# 16A-01.net
KiCad netlist of a schematic drawn in EAGLE
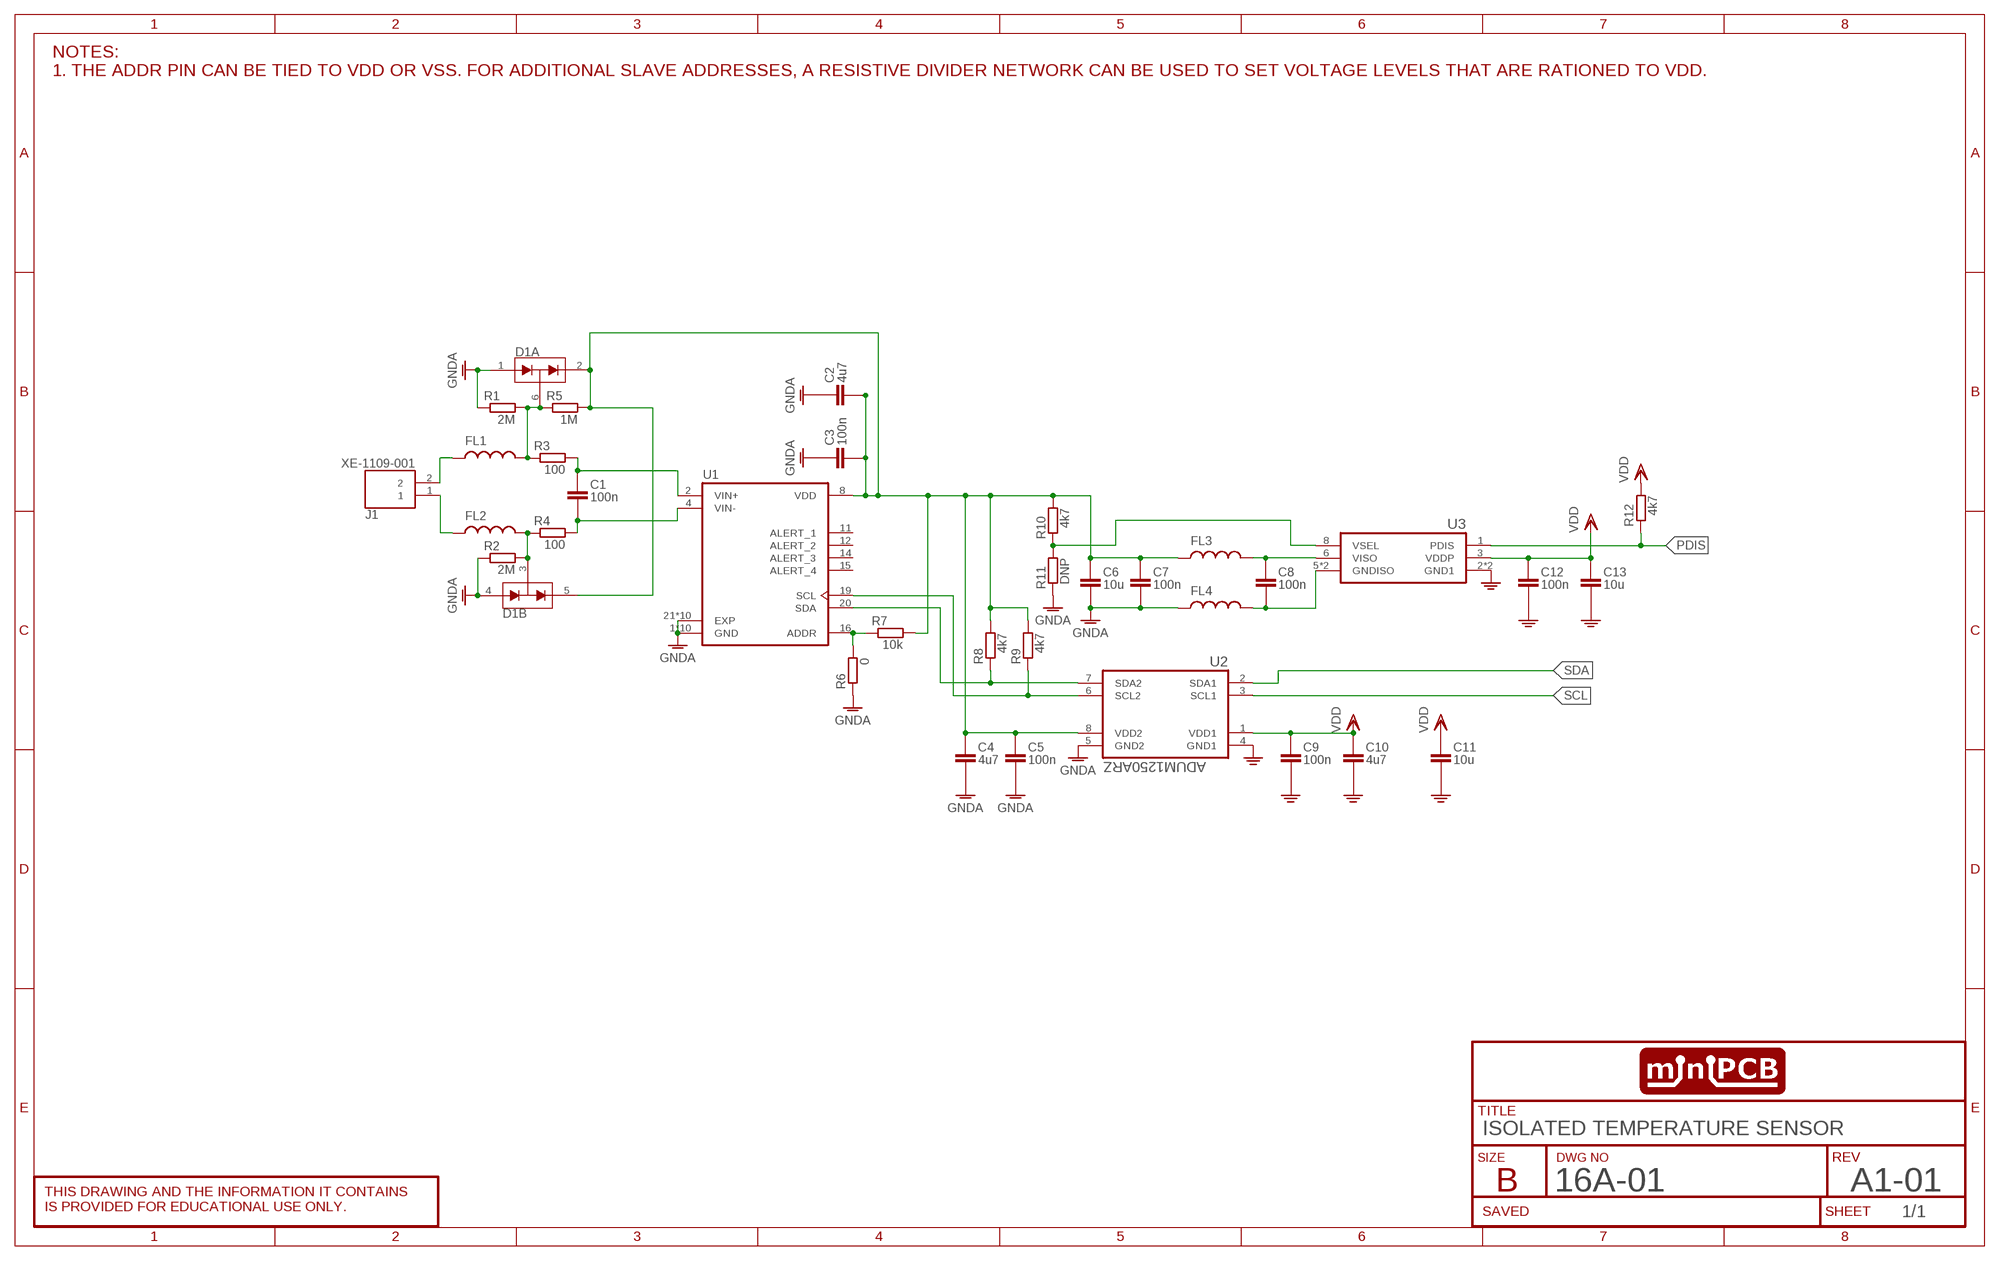
[diagram p0: schematic, sheet 1]

(export (version "E")
  (design (tool "Eeschema 10.0.6"))
  (components
    (comp (ref "C1")
      (value "100n")
      (footprint "eagle-import:C0402")
      (libsource (lib "eagle-import") (part "CAPACITOR0402"))
    )
    (comp (ref "C2")
      (value "4u7")
      (footprint "eagle-import:C0402")
      (libsource (lib "eagle-import") (part "CAPACITOR0402"))
    )
    (comp (ref "C3")
      (value "100n")
      (footprint "eagle-import:C0402")
      (libsource (lib "eagle-import") (part "CAPACITOR0402"))
    )
    (comp (ref "C4")
      (value "4u7")
      (footprint "eagle-import:C0402")
      (libsource (lib "eagle-import") (part "CAPACITOR0402"))
    )
    (comp (ref "C5")
      (value "100n")
      (footprint "eagle-import:C0402")
      (libsource (lib "eagle-import") (part "CAPACITOR0402"))
    )
    (comp (ref "C6")
      (value "10u")
      (footprint "eagle-import:C0805")
      (libsource (lib "eagle-import") (part "CAPACITORSMD"))
    )
    (comp (ref "C7")
      (value "100n")
      (footprint "eagle-import:C0402")
      (libsource (lib "eagle-import") (part "CAPACITOR0402"))
    )
    (comp (ref "C8")
      (value "100n")
      (footprint "eagle-import:C0402")
      (libsource (lib "eagle-import") (part "CAPACITOR0402"))
    )
    (comp (ref "C9")
      (value "100n")
      (footprint "eagle-import:C0402")
      (libsource (lib "eagle-import") (part "CAPACITOR0402"))
    )
    (comp (ref "C10")
      (value "4u7")
      (footprint "eagle-import:C0402")
      (libsource (lib "eagle-import") (part "CAPACITOR0402"))
    )
    (comp (ref "C11")
      (value "10u")
      (footprint "eagle-import:C0805")
      (libsource (lib "eagle-import") (part "CAPACITORSMD"))
    )
    (comp (ref "C12")
      (value "100n")
      (footprint "eagle-import:C0402")
      (libsource (lib "eagle-import") (part "CAPACITOR0402"))
    )
    (comp (ref "C13")
      (value "10u")
      (footprint "eagle-import:C0805")
      (libsource (lib "eagle-import") (part "CAPACITORSMD"))
    )
    (comp (ref "D1")
      (value "SDA004-7")
      (footprint "eagle-import:SOT363")
      (libsource (lib "eagle-import") (part "SDA004-7"))
    )
    (comp (ref "FL1")
      (value "BLM03HG601SZ1D")
      (footprint "eagle-import:R0402")
      (libsource (lib "eagle-import") (part "BLM03HG601SZ1D"))
    )
    (comp (ref "FL2")
      (value "BLM03HG601SZ1D")
      (footprint "eagle-import:R0402")
      (libsource (lib "eagle-import") (part "BLM03HG601SZ1D"))
    )
    (comp (ref "FL3")
      (value "BLM03HG601SZ1D")
      (footprint "eagle-import:R0402")
      (libsource (lib "eagle-import") (part "BLM03HG601SZ1D"))
    )
    (comp (ref "FL4")
      (value "BLM03HG601SZ1D")
      (footprint "eagle-import:R0402")
      (libsource (lib "eagle-import") (part "BLM03HG601SZ1D"))
    )
    (comp (ref "J1")
      (value "XE-1109-001")
      (footprint "eagle-import:XE-1109-001")
      (libsource (lib "eagle-import") (part "XE-1109-001"))
    )
    (comp (ref "R1")
      (value "2M")
      (footprint "eagle-import:R0402")
      (libsource (lib "eagle-import") (part "RESISTOR0402"))
    )
    (comp (ref "R2")
      (value "2M")
      (footprint "eagle-import:R0402")
      (libsource (lib "eagle-import") (part "RESISTOR0402"))
    )
    (comp (ref "R3")
      (value "100")
      (footprint "eagle-import:R0402")
      (libsource (lib "eagle-import") (part "RESISTOR0402"))
    )
    (comp (ref "R4")
      (value "100")
      (footprint "eagle-import:R0402")
      (libsource (lib "eagle-import") (part "RESISTOR0402"))
    )
    (comp (ref "R5")
      (value "1M")
      (footprint "eagle-import:R0402")
      (libsource (lib "eagle-import") (part "RESISTOR0402"))
    )
    (comp (ref "R6")
      (value "0")
      (footprint "eagle-import:R0402")
      (libsource (lib "eagle-import") (part "RESISTOR0402"))
    )
    (comp (ref "R7")
      (value "10k")
      (footprint "eagle-import:R0402")
      (libsource (lib "eagle-import") (part "RESISTOR0402"))
    )
    (comp (ref "R8")
      (value "4k7")
      (footprint "eagle-import:R0402")
      (libsource (lib "eagle-import") (part "RESISTOR0402"))
    )
    (comp (ref "R9")
      (value "4k7")
      (footprint "eagle-import:R0402")
      (libsource (lib "eagle-import") (part "RESISTOR0402"))
    )
    (comp (ref "R10")
      (value "4k7")
      (footprint "eagle-import:R0402")
      (libsource (lib "eagle-import") (part "RESISTOR0402"))
    )
    (comp (ref "R11")
      (value "DNP")
      (footprint "eagle-import:R0402")
      (libsource (lib "eagle-import") (part "RESISTOR0402"))
    )
    (comp (ref "R12")
      (value "4k7")
      (footprint "eagle-import:R0402")
      (libsource (lib "eagle-import") (part "RESISTOR0402"))
    )
    (comp (ref "U1")
      (value "MCP9600T-I/MX")
      (footprint "eagle-import:QFN65P500X500X100-21N_MCP9600T-I_MX")
      (fields (field (name "MF") "Microchip Technology"))
      (libsource (lib "eagle-import") (part "MCP9600T-I/MX"))
    )
    (comp (ref "U2")
      (value "ADUM1250ARZ")
      (footprint "eagle-import:SOIC127P600X175-8N")
      (fields (field (name "MF") "Analog Devices"))
      (libsource (lib "eagle-import") (part "ADUM1250ARZ"))
    )
    (comp (ref "U3")
      (value "ADUM6280")
      (footprint "eagle-import:SOIC127P600X175-8N")
      (libsource (lib "eagle-import") (part "ADUM6280"))
    )
  )
  (nets
    (net (code "1") (name "GND") (class "Default")
      (node (ref "C10") (pin "2") (pinfunction "-_2") (pintype "passive"))
      (node (ref "C11") (pin "2ASDF") (pinfunction "-_2ASDF") (pintype "passive"))
      (node (ref "C12") (pin "2") (pinfunction "-_2") (pintype "passive"))
      (node (ref "C13") (pin "2ASDF") (pinfunction "-_2ASDF") (pintype "passive"))
      (node (ref "C9") (pin "2") (pinfunction "-_2") (pintype "passive"))
      (node (ref "U2") (pin "4") (pinfunction "GND1_4") (pintype "passive"))
      (node (ref "U3") (pin "2") (pinfunction "GND1_2") (pintype "passive"))
      (node (ref "U3") (pin "4") (pinfunction "GND1_4") (pintype "passive"))
    )
    (net (code "2") (name "GNDA") (class "Default")
      (node (ref "C2") (pin "1") (pinfunction "+_1") (pintype "passive"))
      (node (ref "C3") (pin "1") (pinfunction "+_1") (pintype "passive"))
      (node (ref "C4") (pin "2") (pinfunction "-_2") (pintype "passive"))
      (node (ref "C5") (pin "2") (pinfunction "-_2") (pintype "passive"))
      (node (ref "C6") (pin "2ASDF") (pinfunction "-_2ASDF") (pintype "passive"))
      (node (ref "C7") (pin "2") (pinfunction "-_2") (pintype "passive"))
      (node (ref "D1") (pin "1") (pinfunction "A1_1") (pintype "bidirectional"))
      (node (ref "D1") (pin "4") (pinfunction "A1_4") (pintype "bidirectional"))
      (node (ref "FL4") (pin "1") (pinfunction "1_1") (pintype "passive"))
      (node (ref "R1") (pin "1") (pinfunction "1_1") (pintype "passive"))
      (node (ref "R11") (pin "1") (pinfunction "1_1") (pintype "passive"))
      (node (ref "R2") (pin "1") (pinfunction "1_1") (pintype "passive"))
      (node (ref "R6") (pin "1") (pinfunction "1_1") (pintype "passive"))
      (node (ref "U1") (pin "1") (pinfunction "GND_1") (pintype "power_in"))
      (node (ref "U1") (pin "10") (pinfunction "GND_10") (pintype "power_in"))
      (node (ref "U1") (pin "13") (pinfunction "GND_13") (pintype "power_in"))
      (node (ref "U1") (pin "17") (pinfunction "GND_17") (pintype "power_in"))
      (node (ref "U1") (pin "18") (pinfunction "GND_18") (pintype "power_in"))
      (node (ref "U1") (pin "21") (pinfunction "EXP_21") (pintype "power_in"))
      (node (ref "U1") (pin "22") (pinfunction "EXP_22") (pintype "power_in"))
      (node (ref "U1") (pin "23") (pinfunction "EXP_23") (pintype "power_in"))
      (node (ref "U1") (pin "24") (pinfunction "EXP_24") (pintype "power_in"))
      (node (ref "U1") (pin "25") (pinfunction "EXP_25") (pintype "power_in"))
      (node (ref "U1") (pin "26") (pinfunction "EXP_26") (pintype "power_in"))
      (node (ref "U1") (pin "27") (pinfunction "EXP_27") (pintype "power_in"))
      (node (ref "U1") (pin "28") (pinfunction "EXP_28") (pintype "power_in"))
      (node (ref "U1") (pin "29") (pinfunction "EXP_29") (pintype "power_in"))
      (node (ref "U1") (pin "3") (pinfunction "GND_3") (pintype "power_in"))
      (node (ref "U1") (pin "30") (pinfunction "EXP_30") (pintype "power_in"))
      (node (ref "U1") (pin "5") (pinfunction "GND_5") (pintype "power_in"))
      (node (ref "U1") (pin "6") (pinfunction "GND_6") (pintype "power_in"))
      (node (ref "U1") (pin "7") (pinfunction "GND_7") (pintype "power_in"))
      (node (ref "U1") (pin "9") (pinfunction "GND_9") (pintype "power_in"))
      (node (ref "U2") (pin "5") (pinfunction "GND2_5") (pintype "passive"))
    )
    (net (code "3") (name "Net-(C1-+)") (class "Default")
      (node (ref "C1") (pin "1") (pinfunction "+_1") (pintype "passive"))
      (node (ref "R3") (pin "2") (pinfunction "2_2") (pintype "passive"))
      (node (ref "U1") (pin "2") (pinfunction "VIN+_2") (pintype "input"))
    )
    (net (code "4") (name "Net-(C1--)") (class "Default")
      (node (ref "C1") (pin "2") (pinfunction "-_2") (pintype "passive"))
      (node (ref "R4") (pin "2") (pinfunction "2_2") (pintype "passive"))
      (node (ref "U1") (pin "4") (pinfunction "VIN-_4") (pintype "input"))
    )
    (net (code "5") (name "Net-(C2--)") (class "Default")
      (node (ref "C2") (pin "2") (pinfunction "-_2") (pintype "passive"))
      (node (ref "C3") (pin "2") (pinfunction "-_2") (pintype "passive"))
      (node (ref "C4") (pin "1") (pinfunction "+_1") (pintype "passive"))
      (node (ref "C5") (pin "1") (pinfunction "+_1") (pintype "passive"))
      (node (ref "C6") (pin "1ASD") (pinfunction "+_1ASD") (pintype "passive"))
      (node (ref "C7") (pin "1") (pinfunction "+_1") (pintype "passive"))
      (node (ref "D1") (pin "2") (pinfunction "C2_2") (pintype "bidirectional"))
      (node (ref "D1") (pin "5") (pinfunction "C2_5") (pintype "bidirectional"))
      (node (ref "FL3") (pin "1") (pinfunction "1_1") (pintype "passive"))
      (node (ref "R10") (pin "2") (pinfunction "2_2") (pintype "passive"))
      (node (ref "R5") (pin "2") (pinfunction "2_2") (pintype "passive"))
      (node (ref "R7") (pin "2") (pinfunction "2_2") (pintype "passive"))
      (node (ref "R8") (pin "2") (pinfunction "2_2") (pintype "passive"))
      (node (ref "R9") (pin "2") (pinfunction "2_2") (pintype "passive"))
      (node (ref "U1") (pin "8") (pinfunction "VDD_8") (pintype "power_in"))
      (node (ref "U2") (pin "8") (pinfunction "VDD2_8") (pintype "power_in"))
    )
    (net (code "6") (name "Net-(C8-+)") (class "Default")
      (node (ref "C8") (pin "1") (pinfunction "+_1") (pintype "passive"))
      (node (ref "FL3") (pin "2") (pinfunction "2_2") (pintype "passive"))
      (node (ref "U3") (pin "6") (pinfunction "VISO_6") (pintype "power_in"))
    )
    (net (code "7") (name "Net-(C8--)") (class "Default")
      (node (ref "C8") (pin "2") (pinfunction "-_2") (pintype "passive"))
      (node (ref "FL4") (pin "2") (pinfunction "2_2") (pintype "passive"))
      (node (ref "U3") (pin "5") (pinfunction "GNDISO_5") (pintype "passive"))
      (node (ref "U3") (pin "7") (pinfunction "GNDISO_7") (pintype "passive"))
    )
    (net (code "8") (name "Net-(D1A-COM)") (class "Default")
      (node (ref "D1") (pin "6") (pinfunction "COM_6") (pintype "bidirectional"))
      (node (ref "FL1") (pin "2") (pinfunction "2_2") (pintype "passive"))
      (node (ref "R1") (pin "2") (pinfunction "2_2") (pintype "passive"))
      (node (ref "R3") (pin "1") (pinfunction "1_1") (pintype "passive"))
      (node (ref "R5") (pin "1") (pinfunction "1_1") (pintype "passive"))
    )
    (net (code "9") (name "Net-(D1B-COM)") (class "Default")
      (node (ref "D1") (pin "3") (pinfunction "COM_3") (pintype "bidirectional"))
      (node (ref "FL2") (pin "2") (pinfunction "2_2") (pintype "passive"))
      (node (ref "R2") (pin "2") (pinfunction "2_2") (pintype "passive"))
      (node (ref "R4") (pin "1") (pinfunction "1_1") (pintype "passive"))
    )
    (net (code "10") (name "Net-(FL1-Pad1)") (class "Default")
      (node (ref "FL1") (pin "1") (pinfunction "1_1") (pintype "passive"))
      (node (ref "J1") (pin "2") (pinfunction "2_2") (pintype "bidirectional"))
    )
    (net (code "11") (name "Net-(FL2-Pad1)") (class "Default")
      (node (ref "FL2") (pin "1") (pinfunction "1_1") (pintype "passive"))
      (node (ref "J1") (pin "1") (pinfunction "1_1") (pintype "bidirectional"))
    )
    (net (code "12") (name "Net-(U1-ADDR)") (class "Default")
      (node (ref "R6") (pin "2") (pinfunction "2_2") (pintype "passive"))
      (node (ref "R7") (pin "1") (pinfunction "1_1") (pintype "passive"))
      (node (ref "U1") (pin "16") (pinfunction "ADDR_16") (pintype "input"))
    )
    (net (code "13") (name "Net-(U1-SCL)") (class "Default")
      (node (ref "R9") (pin "1") (pinfunction "1_1") (pintype "passive"))
      (node (ref "U1") (pin "19") (pinfunction "SCL_19") (pintype "input"))
      (node (ref "U2") (pin "6") (pinfunction "SCL2_6") (pintype "input"))
    )
    (net (code "14") (name "Net-(U1-SDA)") (class "Default")
      (node (ref "R8") (pin "1") (pinfunction "1_1") (pintype "passive"))
      (node (ref "U1") (pin "20") (pinfunction "SDA_20") (pintype "bidirectional"))
      (node (ref "U2") (pin "7") (pinfunction "SDA2_7") (pintype "bidirectional"))
    )
    (net (code "15") (name "Net-(U3-VSEL)") (class "Default")
      (node (ref "R10") (pin "1") (pinfunction "1_1") (pintype "passive"))
      (node (ref "R11") (pin "2") (pinfunction "2_2") (pintype "passive"))
      (node (ref "U3") (pin "8") (pinfunction "VSEL_8") (pintype "power_in"))
    )
    (net (code "16") (name "PDIS") (class "Default")
      (node (ref "R12") (pin "1") (pinfunction "1_1") (pintype "passive"))
      (node (ref "U3") (pin "1") (pinfunction "PDIS_1") (pintype "power_in"))
    )
    (net (code "17") (name "SCL") (class "Default")
      (node (ref "U2") (pin "3") (pinfunction "SCL1_3") (pintype "input"))
    )
    (net (code "18") (name "SDA") (class "Default")
      (node (ref "U2") (pin "2") (pinfunction "SDA1_2") (pintype "bidirectional"))
    )
    (net (code "19") (name "VDD") (class "Default")
      (node (ref "C10") (pin "1") (pinfunction "+_1") (pintype "passive"))
      (node (ref "C11") (pin "1ASD") (pinfunction "+_1ASD") (pintype "passive"))
      (node (ref "C12") (pin "1") (pinfunction "+_1") (pintype "passive"))
      (node (ref "C13") (pin "1ASD") (pinfunction "+_1ASD") (pintype "passive"))
      (node (ref "C9") (pin "1") (pinfunction "+_1") (pintype "passive"))
      (node (ref "R12") (pin "2") (pinfunction "2_2") (pintype "passive"))
      (node (ref "U2") (pin "1") (pinfunction "VDD1_1") (pintype "power_in"))
      (node (ref "U3") (pin "3") (pinfunction "VDDP_3") (pintype "bidirectional"))
    )
    (net (code "20") (name "unconnected-(U1-ALERT_1-Pad11)") (class "Default")
      (node (ref "U1") (pin "11") (pinfunction "ALERT_1_11") (pintype "output"))
    )
    (net (code "21") (name "unconnected-(U1-ALERT_2-Pad12)") (class "Default")
      (node (ref "U1") (pin "12") (pinfunction "ALERT_2_12") (pintype "output"))
    )
    (net (code "22") (name "unconnected-(U1-ALERT_3-Pad14)") (class "Default")
      (node (ref "U1") (pin "14") (pinfunction "ALERT_3_14") (pintype "output"))
    )
    (net (code "23") (name "unconnected-(U1-ALERT_4-Pad15)") (class "Default")
      (node (ref "U1") (pin "15") (pinfunction "ALERT_4_15") (pintype "output"))
    )
  )
)
